# 17_CAM_CONNECTOR.net
KiCad netlist of a schematic drawn in Altium Designer
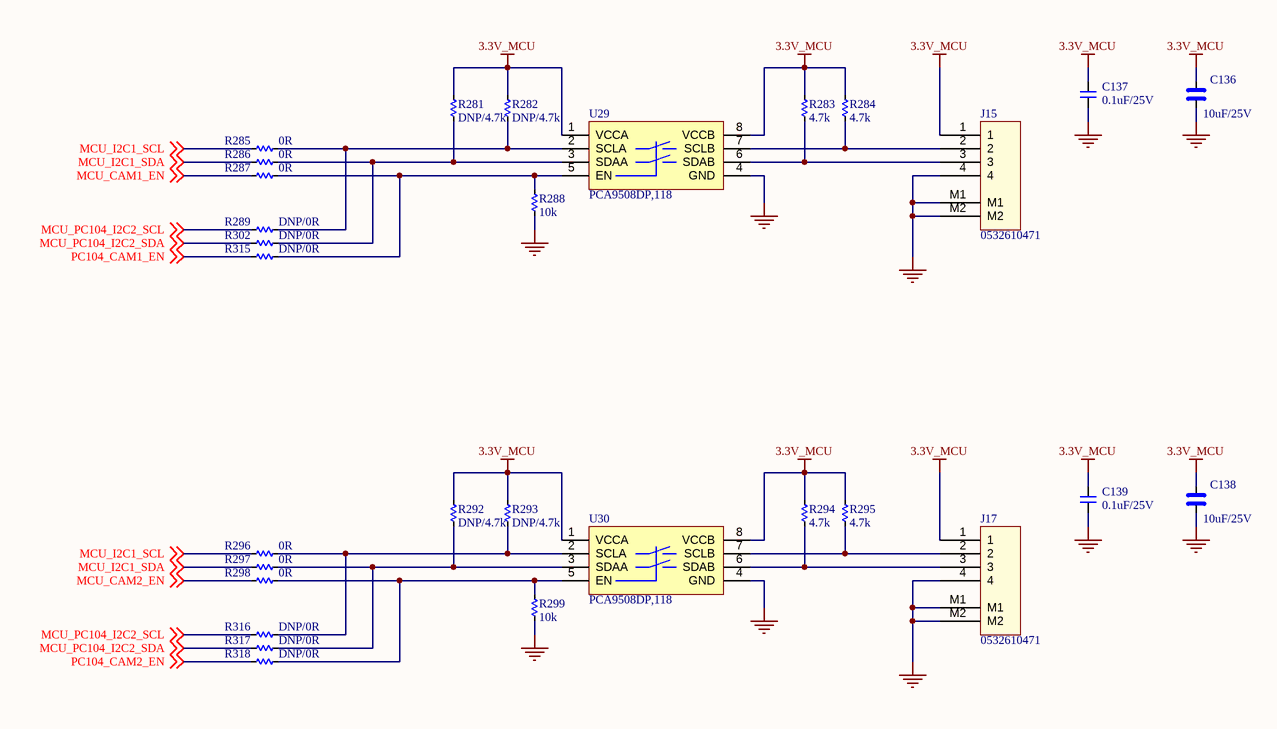
[diagram p0: 17_CAM_CONNECTOR.SchDoc]

(export (version "E")
  (design (tool "Eeschema 10.0.6"))
  (components
    (comp (ref "C136")
      (value "10uF/25V")
      (footprint "CAP_C_2012X110")
      (description "CAP High Value")
      (libsource (lib "LABLIB") (part "_CAP_C_High_2"))
    )
    (comp (ref "C137")
      (value "0.1uF/25V")
      (footprint "CAP_C_1005X60")
      (description "CAP")
      (libsource (lib "LABLIB") (part "_CAP_C_2"))
    )
    (comp (ref "C138")
      (value "10uF/25V")
      (footprint "CAP_C_2012X110")
      (description "CAP High Value")
      (libsource (lib "LABLIB") (part "_CAP_C_High_2"))
    )
    (comp (ref "C139")
      (value "0.1uF/25V")
      (footprint "CAP_C_1005X60")
      (description "CAP")
      (libsource (lib "LABLIB") (part "_CAP_C_2"))
    )
    (comp (ref "J15")
      (value "0532610471")
      (footprint "MOLEX_0532610471")
      (libsource (lib "BEE-DAL_EXP_sche") (part "Header 4x1_2M_1"))
    )
    (comp (ref "J17")
      (value "0532610471")
      (footprint "MOLEX_0532610471")
      (libsource (lib "BEE-DAL_EXP_sche") (part "Header 4x1_2M_1"))
    )
    (comp (ref "R281")
      (value "DNP/4.7k")
      (footprint "RES_C_1005X40")
      (description "RES")
      (libsource (lib "LABLIB") (part "_RES_B_2"))
    )
    (comp (ref "R282")
      (value "DNP/4.7k")
      (footprint "RES_C_1005X40")
      (description "RES")
      (libsource (lib "LABLIB") (part "_RES_B_2"))
    )
    (comp (ref "R283")
      (value "4.7k")
      (footprint "RES_C_1005X40")
      (description "RES")
      (libsource (lib "LABLIB") (part "_RES_B_2"))
    )
    (comp (ref "R284")
      (value "4.7k")
      (footprint "RES_C_1005X40")
      (description "RES")
      (libsource (lib "LABLIB") (part "_RES_B_2"))
    )
    (comp (ref "R285")
      (value "0R")
      (footprint "RES_C_1005X40")
      (description "RES")
      (libsource (lib "LABLIB") (part "_RES_B_2"))
    )
    (comp (ref "R286")
      (value "0R")
      (footprint "RES_C_1005X40")
      (description "RES")
      (libsource (lib "LABLIB") (part "_RES_B_2"))
    )
    (comp (ref "R287")
      (value "0R")
      (footprint "RES_C_1005X40")
      (description "RES")
      (libsource (lib "LABLIB") (part "_RES_B_2"))
    )
    (comp (ref "R288")
      (value "10k")
      (footprint "RES_C_1005X40")
      (description "RES")
      (libsource (lib "LABLIB") (part "_RES_B_2"))
    )
    (comp (ref "R289")
      (value "DNP/0R")
      (footprint "RES_C_1005X40")
      (description "RES")
      (libsource (lib "LABLIB") (part "_RES_B_2"))
    )
    (comp (ref "R292")
      (value "DNP/4.7k")
      (footprint "RES_C_1005X40")
      (description "RES")
      (libsource (lib "LABLIB") (part "_RES_B_2"))
    )
    (comp (ref "R293")
      (value "DNP/4.7k")
      (footprint "RES_C_1005X40")
      (description "RES")
      (libsource (lib "LABLIB") (part "_RES_B_2"))
    )
    (comp (ref "R294")
      (value "4.7k")
      (footprint "RES_C_1005X40")
      (description "RES")
      (libsource (lib "LABLIB") (part "_RES_B_2"))
    )
    (comp (ref "R295")
      (value "4.7k")
      (footprint "RES_C_1005X40")
      (description "RES")
      (libsource (lib "LABLIB") (part "_RES_B_2"))
    )
    (comp (ref "R296")
      (value "0R")
      (footprint "RES_C_1005X40")
      (description "RES")
      (libsource (lib "LABLIB") (part "_RES_B_2"))
    )
    (comp (ref "R297")
      (value "0R")
      (footprint "RES_C_1005X40")
      (description "RES")
      (libsource (lib "LABLIB") (part "_RES_B_2"))
    )
    (comp (ref "R298")
      (value "0R")
      (footprint "RES_C_1005X40")
      (description "RES")
      (libsource (lib "LABLIB") (part "_RES_B_2"))
    )
    (comp (ref "R299")
      (value "10k")
      (footprint "RES_C_1005X40")
      (description "RES")
      (libsource (lib "LABLIB") (part "_RES_B_2"))
    )
    (comp (ref "R302")
      (value "DNP/0R")
      (footprint "RES_C_1005X40")
      (description "RES")
      (libsource (lib "LABLIB") (part "_RES_B_2"))
    )
    (comp (ref "R315")
      (value "DNP/0R")
      (footprint "RES_C_1005X40")
      (description "RES")
      (libsource (lib "LABLIB") (part "_RES_B_2"))
    )
    (comp (ref "R316")
      (value "DNP/0R")
      (footprint "RES_C_1005X40")
      (description "RES")
      (libsource (lib "LABLIB") (part "_RES_B_2"))
    )
    (comp (ref "R317")
      (value "DNP/0R")
      (footprint "RES_C_1005X40")
      (description "RES")
      (libsource (lib "LABLIB") (part "_RES_B_2"))
    )
    (comp (ref "R318")
      (value "DNP/0R")
      (footprint "RES_C_1005X40")
      (description "RES")
      (libsource (lib "LABLIB") (part "_RES_B_2"))
    )
    (comp (ref "U29")
      (value "PCA9508DP,118")
      (footprint "TSOP8")
      (libsource (lib "BEE-DAL_EXP_sche") (part "PCA9508DP,118"))
    )
    (comp (ref "U30")
      (value "PCA9508DP,118")
      (footprint "TSOP8")
      (libsource (lib "BEE-DAL_EXP_sche") (part "PCA9508DP,118"))
    )
  )
  (nets
    (net (code "1") (name "3.3V_MCU") (class "Default")
      (node (ref "C136") (pin "1") (pinfunction "1_1") (pintype "passive"))
      (node (ref "C137") (pin "2") (pinfunction "2_2") (pintype "passive"))
      (node (ref "C138") (pin "1") (pinfunction "1_1") (pintype "passive"))
      (node (ref "C139") (pin "2") (pinfunction "2_2") (pintype "passive"))
      (node (ref "J15") (pin "1") (pinfunction "1_1") (pintype "passive"))
      (node (ref "J17") (pin "1") (pinfunction "1_1") (pintype "passive"))
      (node (ref "R281") (pin "1") (pinfunction "1_1") (pintype "passive"))
      (node (ref "R282") (pin "1") (pinfunction "1_1") (pintype "passive"))
      (node (ref "R283") (pin "1") (pinfunction "1_1") (pintype "passive"))
      (node (ref "R284") (pin "1") (pinfunction "1_1") (pintype "passive"))
      (node (ref "R292") (pin "1") (pinfunction "1_1") (pintype "passive"))
      (node (ref "R293") (pin "1") (pinfunction "1_1") (pintype "passive"))
      (node (ref "R294") (pin "1") (pinfunction "1_1") (pintype "passive"))
      (node (ref "R295") (pin "1") (pinfunction "1_1") (pintype "passive"))
      (node (ref "U29") (pin "1") (pinfunction "VCCA_1") (pintype "passive"))
      (node (ref "U29") (pin "8") (pinfunction "VCCB_8") (pintype "passive"))
      (node (ref "U30") (pin "1") (pinfunction "VCCA_1") (pintype "passive"))
      (node (ref "U30") (pin "8") (pinfunction "VCCB_8") (pintype "passive"))
    )
    (net (code "2") (name "GND") (class "Default")
      (node (ref "C136") (pin "2") (pinfunction "2_2") (pintype "passive"))
      (node (ref "C137") (pin "1") (pinfunction "1_1") (pintype "passive"))
      (node (ref "C138") (pin "2") (pinfunction "2_2") (pintype "passive"))
      (node (ref "C139") (pin "1") (pinfunction "1_1") (pintype "passive"))
      (node (ref "J15") (pin "4") (pinfunction "4_4") (pintype "passive"))
      (node (ref "J15") (pin "M1") (pinfunction "M1_M1") (pintype "passive"))
      (node (ref "J15") (pin "M2") (pinfunction "M2_M2") (pintype "passive"))
      (node (ref "J17") (pin "4") (pinfunction "4_4") (pintype "passive"))
      (node (ref "J17") (pin "M1") (pinfunction "M1_M1") (pintype "passive"))
      (node (ref "J17") (pin "M2") (pinfunction "M2_M2") (pintype "passive"))
      (node (ref "R288") (pin "2") (pinfunction "2_2") (pintype "passive"))
      (node (ref "R299") (pin "2") (pinfunction "2_2") (pintype "passive"))
      (node (ref "U29") (pin "4") (pinfunction "GND_4") (pintype "passive"))
      (node (ref "U30") (pin "4") (pinfunction "GND_4") (pintype "passive"))
    )
    (net (code "3") (name "MCU_CAM1_EN") (class "Default")
      (node (ref "R287") (pin "1") (pinfunction "1_1") (pintype "passive"))
    )
    (net (code "4") (name "MCU_CAM2_EN") (class "Default")
      (node (ref "R298") (pin "1") (pinfunction "1_1") (pintype "passive"))
    )
    (net (code "5") (name "MCU_I2C1_SCL") (class "Default")
      (node (ref "R285") (pin "1") (pinfunction "1_1") (pintype "passive"))
      (node (ref "R296") (pin "1") (pinfunction "1_1") (pintype "passive"))
    )
    (net (code "6") (name "MCU_I2C1_SDA") (class "Default")
      (node (ref "R286") (pin "1") (pinfunction "1_1") (pintype "passive"))
      (node (ref "R297") (pin "1") (pinfunction "1_1") (pintype "passive"))
    )
    (net (code "7") (name "MCU_PC104_I2C2_SCL") (class "Default")
      (node (ref "R289") (pin "1") (pinfunction "1_1") (pintype "passive"))
      (node (ref "R316") (pin "1") (pinfunction "1_1") (pintype "passive"))
    )
    (net (code "8") (name "MCU_PC104_I2C2_SDA") (class "Default")
      (node (ref "R302") (pin "1") (pinfunction "1_1") (pintype "passive"))
      (node (ref "R317") (pin "1") (pinfunction "1_1") (pintype "passive"))
    )
    (net (code "9") (name "Net-(U29-EN)") (class "Default")
      (node (ref "R287") (pin "2") (pinfunction "2_2") (pintype "passive"))
      (node (ref "R288") (pin "1") (pinfunction "1_1") (pintype "passive"))
      (node (ref "R315") (pin "2") (pinfunction "2_2") (pintype "passive"))
      (node (ref "U29") (pin "5") (pinfunction "EN_5") (pintype "passive"))
    )
    (net (code "10") (name "Net-(U29-SCLA)") (class "Default")
      (node (ref "R282") (pin "2") (pinfunction "2_2") (pintype "passive"))
      (node (ref "R285") (pin "2") (pinfunction "2_2") (pintype "passive"))
      (node (ref "R289") (pin "2") (pinfunction "2_2") (pintype "passive"))
      (node (ref "U29") (pin "2") (pinfunction "SCLA_2") (pintype "passive"))
    )
    (net (code "11") (name "Net-(U29-SCLB)") (class "Default")
      (node (ref "J15") (pin "2") (pinfunction "2_2") (pintype "passive"))
      (node (ref "R284") (pin "2") (pinfunction "2_2") (pintype "passive"))
      (node (ref "U29") (pin "7") (pinfunction "SCLB_7") (pintype "passive"))
    )
    (net (code "12") (name "Net-(U29-SDAA)") (class "Default")
      (node (ref "R281") (pin "2") (pinfunction "2_2") (pintype "passive"))
      (node (ref "R286") (pin "2") (pinfunction "2_2") (pintype "passive"))
      (node (ref "R302") (pin "2") (pinfunction "2_2") (pintype "passive"))
      (node (ref "U29") (pin "3") (pinfunction "SDAA_3") (pintype "passive"))
    )
    (net (code "13") (name "Net-(U29-SDAB)") (class "Default")
      (node (ref "J15") (pin "3") (pinfunction "3_3") (pintype "passive"))
      (node (ref "R283") (pin "2") (pinfunction "2_2") (pintype "passive"))
      (node (ref "U29") (pin "6") (pinfunction "SDAB_6") (pintype "passive"))
    )
    (net (code "14") (name "Net-(U30-EN)") (class "Default")
      (node (ref "R298") (pin "2") (pinfunction "2_2") (pintype "passive"))
      (node (ref "R299") (pin "1") (pinfunction "1_1") (pintype "passive"))
      (node (ref "R318") (pin "2") (pinfunction "2_2") (pintype "passive"))
      (node (ref "U30") (pin "5") (pinfunction "EN_5") (pintype "passive"))
    )
    (net (code "15") (name "Net-(U30-SCLA)") (class "Default")
      (node (ref "R293") (pin "2") (pinfunction "2_2") (pintype "passive"))
      (node (ref "R296") (pin "2") (pinfunction "2_2") (pintype "passive"))
      (node (ref "R316") (pin "2") (pinfunction "2_2") (pintype "passive"))
      (node (ref "U30") (pin "2") (pinfunction "SCLA_2") (pintype "passive"))
    )
    (net (code "16") (name "Net-(U30-SCLB)") (class "Default")
      (node (ref "J17") (pin "2") (pinfunction "2_2") (pintype "passive"))
      (node (ref "R295") (pin "2") (pinfunction "2_2") (pintype "passive"))
      (node (ref "U30") (pin "7") (pinfunction "SCLB_7") (pintype "passive"))
    )
    (net (code "17") (name "Net-(U30-SDAA)") (class "Default")
      (node (ref "R292") (pin "2") (pinfunction "2_2") (pintype "passive"))
      (node (ref "R297") (pin "2") (pinfunction "2_2") (pintype "passive"))
      (node (ref "R317") (pin "2") (pinfunction "2_2") (pintype "passive"))
      (node (ref "U30") (pin "3") (pinfunction "SDAA_3") (pintype "passive"))
    )
    (net (code "18") (name "Net-(U30-SDAB)") (class "Default")
      (node (ref "J17") (pin "3") (pinfunction "3_3") (pintype "passive"))
      (node (ref "R294") (pin "2") (pinfunction "2_2") (pintype "passive"))
      (node (ref "U30") (pin "6") (pinfunction "SDAB_6") (pintype "passive"))
    )
    (net (code "19") (name "PC104_CAM1_EN") (class "Default")
      (node (ref "R315") (pin "1") (pinfunction "1_1") (pintype "passive"))
    )
    (net (code "20") (name "PC104_CAM2_EN") (class "Default")
      (node (ref "R318") (pin "1") (pinfunction "1_1") (pintype "passive"))
    )
  )
)
